# Input_amplifiers.net
KiCad netlist of a schematic drawn in Altium Designer
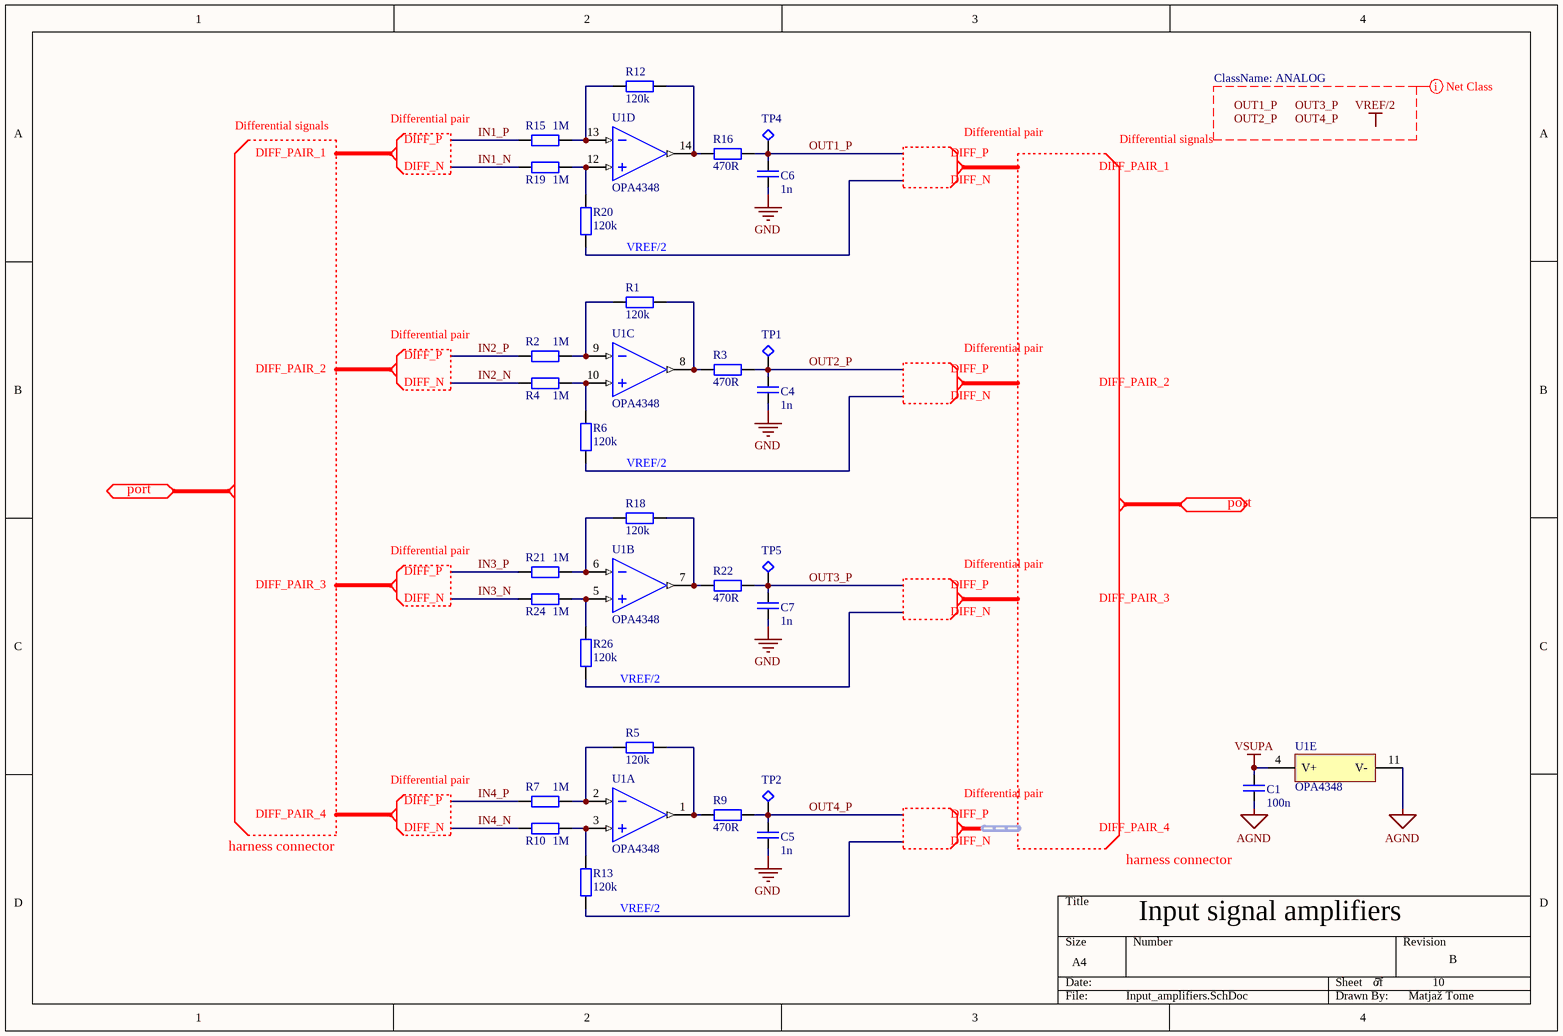
[diagram p0: Input_amplifiers.SchDoc]

(export (version "E")
  (design (tool "Eeschema 10.0.6"))
  (components
    (comp (ref "C1")
      (value "100n")
      (footprint "C_0603")
      (description "Generic capacitor")
      (libsource (lib "DAQ_REV_B") (part "Capacitor"))
    )
    (comp (ref "C4")
      (value "1n")
      (footprint "C_0603")
      (description "Generic capacitor")
      (libsource (lib "DAQ_REV_B") (part "Capacitor"))
    )
    (comp (ref "C5")
      (value "1n")
      (footprint "C_0603")
      (description "Generic capacitor")
      (libsource (lib "DAQ_REV_B") (part "Capacitor"))
    )
    (comp (ref "C6")
      (value "1n")
      (footprint "C_0603")
      (description "Generic capacitor")
      (libsource (lib "DAQ_REV_B") (part "Capacitor"))
    )
    (comp (ref "C7")
      (value "1n")
      (footprint "C_0603")
      (description "Generic capacitor")
      (libsource (lib "DAQ_REV_B") (part "Capacitor"))
    )
    (comp (ref "R1")
      (value "120k")
      (footprint "R_0603")
      (description "Generic resistor")
      (libsource (lib "DAQ_REV_B") (part "Resistor"))
    )
    (comp (ref "R2")
      (value "1M")
      (footprint "R_0603")
      (description "Generic resistor")
      (libsource (lib "DAQ_REV_B") (part "Resistor"))
    )
    (comp (ref "R3")
      (value "470R")
      (footprint "R_0603")
      (description "Generic resistor")
      (libsource (lib "DAQ_REV_B") (part "Resistor"))
    )
    (comp (ref "R4")
      (value "1M")
      (footprint "R_0603")
      (description "Generic resistor")
      (libsource (lib "DAQ_REV_B") (part "Resistor"))
    )
    (comp (ref "R5")
      (value "120k")
      (footprint "R_0603")
      (description "Generic resistor")
      (libsource (lib "DAQ_REV_B") (part "Resistor"))
    )
    (comp (ref "R6")
      (value "120k")
      (footprint "R_0603")
      (description "Generic resistor")
      (libsource (lib "DAQ_REV_B") (part "Resistor"))
    )
    (comp (ref "R7")
      (value "1M")
      (footprint "R_0603")
      (description "Generic resistor")
      (libsource (lib "DAQ_REV_B") (part "Resistor"))
    )
    (comp (ref "R9")
      (value "470R")
      (footprint "R_0603")
      (description "Generic resistor")
      (libsource (lib "DAQ_REV_B") (part "Resistor"))
    )
    (comp (ref "R10")
      (value "1M")
      (footprint "R_0603")
      (description "Generic resistor")
      (libsource (lib "DAQ_REV_B") (part "Resistor"))
    )
    (comp (ref "R12")
      (value "120k")
      (footprint "R_0603")
      (description "Generic resistor")
      (libsource (lib "DAQ_REV_B") (part "Resistor"))
    )
    (comp (ref "R13")
      (value "120k")
      (footprint "R_0603")
      (description "Generic resistor")
      (libsource (lib "DAQ_REV_B") (part "Resistor"))
    )
    (comp (ref "R15")
      (value "1M")
      (footprint "R_0603")
      (description "Generic resistor")
      (libsource (lib "DAQ_REV_B") (part "Resistor"))
    )
    (comp (ref "R16")
      (value "470R")
      (footprint "R_0603")
      (description "Generic resistor")
      (libsource (lib "DAQ_REV_B") (part "Resistor"))
    )
    (comp (ref "R18")
      (value "120k")
      (footprint "R_0603")
      (description "Generic resistor")
      (libsource (lib "DAQ_REV_B") (part "Resistor"))
    )
    (comp (ref "R19")
      (value "1M")
      (footprint "R_0603")
      (description "Generic resistor")
      (libsource (lib "DAQ_REV_B") (part "Resistor"))
    )
    (comp (ref "R20")
      (value "120k")
      (footprint "R_0603")
      (description "Generic resistor")
      (libsource (lib "DAQ_REV_B") (part "Resistor"))
    )
    (comp (ref "R21")
      (value "1M")
      (footprint "R_0603")
      (description "Generic resistor")
      (libsource (lib "DAQ_REV_B") (part "Resistor"))
    )
    (comp (ref "R22")
      (value "470R")
      (footprint "R_0603")
      (description "Generic resistor")
      (libsource (lib "DAQ_REV_B") (part "Resistor"))
    )
    (comp (ref "R24")
      (value "1M")
      (footprint "R_0603")
      (description "Generic resistor")
      (libsource (lib "DAQ_REV_B") (part "Resistor"))
    )
    (comp (ref "R26")
      (value "120k")
      (footprint "R_0603")
      (description "Generic resistor")
      (libsource (lib "DAQ_REV_B") (part "Resistor"))
    )
    (comp (ref "TP1")
      (value "testpoint")
      (footprint "TP1_FULL")
      (description "testpoint 1.5mm diameter no hole")
      (fields (field (name "PART NUMBER") "XXC0006"))
      (libsource (lib "DAQ_REV_B") (part "Test Point"))
    )
    (comp (ref "TP2")
      (value "testpoint")
      (footprint "TP1_FULL")
      (description "testpoint 1.5mm diameter no hole")
      (fields (field (name "PART NUMBER") "XXC0006"))
      (libsource (lib "DAQ_REV_B") (part "Test Point"))
    )
    (comp (ref "TP4")
      (value "testpoint")
      (footprint "TP1_FULL")
      (description "testpoint 1.5mm diameter no hole")
      (fields (field (name "PART NUMBER") "XXC0006"))
      (libsource (lib "DAQ_REV_B") (part "Test Point"))
    )
    (comp (ref "TP5")
      (value "testpoint")
      (footprint "TP1_FULL")
      (description "testpoint 1.5mm diameter no hole")
      (fields (field (name "PART NUMBER") "XXC0006"))
      (libsource (lib "DAQ_REV_B") (part "Test Point"))
    )
    (comp (ref "U1")
      (value "OPA4348")
      (description "1MHz, 45µA, CMOS, Rail-to-Rail OPERATIONAL AMPLIFIERS Value Line Series")
      (fields (field (name "PART NUMBER") "XOG0008") (field (name "MANUFACTURER") "Texas Instruments"))
      (libsource (lib "DAQ_REV_B") (part "OPA4348"))
    )
  )
  (nets
    (net (code "1") (name "/IN1_N") (class "Default") (node (ref "R19") (pin "1") (pintype "passive")))
    (net (code "2") (name "/IN1_P") (class "Default") (node (ref "R15") (pin "1") (pintype "passive")))
    (net (code "3") (name "/IN2_N") (class "Default") (node (ref "R4") (pin "1") (pintype "passive")))
    (net (code "4") (name "/IN2_P") (class "Default") (node (ref "R2") (pin "1") (pintype "passive")))
    (net (code "5") (name "/IN3_N") (class "Default") (node (ref "R24") (pin "1") (pintype "passive")))
    (net (code "6") (name "/IN3_P") (class "Default") (node (ref "R21") (pin "1") (pintype "passive")))
    (net (code "7") (name "/IN4_N") (class "Default") (node (ref "R10") (pin "1") (pintype "passive")))
    (net (code "8") (name "/IN4_P") (class "Default") (node (ref "R7") (pin "1") (pintype "passive")))
    (net (code "9") (name "/OUT1_P") (class "Default")
      (node (ref "C6") (pin "1") (pinfunction "1_1") (pintype "passive"))
      (node (ref "R16") (pin "2") (pintype "passive"))
      (node (ref "TP4") (pin "1") (pinfunction "1_1") (pintype "passive"))
    )
    (net (code "10") (name "/OUT2_P") (class "Default")
      (node (ref "C4") (pin "1") (pinfunction "1_1") (pintype "passive"))
      (node (ref "R3") (pin "2") (pintype "passive"))
      (node (ref "TP1") (pin "1") (pinfunction "1_1") (pintype "passive"))
    )
    (net (code "11") (name "/OUT3_P") (class "Default")
      (node (ref "C7") (pin "1") (pinfunction "1_1") (pintype "passive"))
      (node (ref "R22") (pin "2") (pintype "passive"))
      (node (ref "TP5") (pin "1") (pinfunction "1_1") (pintype "passive"))
    )
    (net (code "12") (name "/OUT4_P") (class "Default")
      (node (ref "C5") (pin "1") (pinfunction "1_1") (pintype "passive"))
      (node (ref "R9") (pin "2") (pintype "passive"))
      (node (ref "TP2") (pin "1") (pinfunction "1_1") (pintype "passive"))
    )
    (net (code "13") (name "AGND") (class "Default")
      (node (ref "C1") (pin "1") (pinfunction "1_1") (pintype "passive"))
      (node (ref "U1") (pin "11") (pinfunction "V-_11") (pintype "power_in"))
    )
    (net (code "14") (name "GND") (class "Default")
      (node (ref "C4") (pin "2") (pinfunction "2_2") (pintype "passive"))
      (node (ref "C5") (pin "2") (pinfunction "2_2") (pintype "passive"))
      (node (ref "C6") (pin "2") (pinfunction "2_2") (pintype "passive"))
      (node (ref "C7") (pin "2") (pinfunction "2_2") (pintype "passive"))
    )
    (net (code "15") (name "Net-(U1A-+IN_A)") (class "Default")
      (node (ref "R10") (pin "2") (pintype "passive"))
      (node (ref "R13") (pin "2") (pintype "passive"))
      (node (ref "U1") (pin "3") (pinfunction "+IN_A_3") (pintype "input"))
    )
    (net (code "16") (name "Net-(U1A--IN_A)") (class "Default")
      (node (ref "R5") (pin "1") (pintype "passive"))
      (node (ref "R7") (pin "2") (pintype "passive"))
      (node (ref "U1") (pin "2") (pinfunction "-IN_A_2") (pintype "input"))
    )
    (net (code "17") (name "Net-(U1A-OUT_A)") (class "Default")
      (node (ref "R5") (pin "2") (pintype "passive"))
      (node (ref "R9") (pin "1") (pintype "passive"))
      (node (ref "U1") (pin "1") (pinfunction "OUT_A_1") (pintype "output"))
    )
    (net (code "18") (name "Net-(U1B-+IN_B)") (class "Default")
      (node (ref "R24") (pin "2") (pintype "passive"))
      (node (ref "R26") (pin "2") (pintype "passive"))
      (node (ref "U1") (pin "5") (pinfunction "+IN_B_5") (pintype "input"))
    )
    (net (code "19") (name "Net-(U1B--IN_B)") (class "Default")
      (node (ref "R18") (pin "1") (pintype "passive"))
      (node (ref "R21") (pin "2") (pintype "passive"))
      (node (ref "U1") (pin "6") (pinfunction "-IN_B_6") (pintype "input"))
    )
    (net (code "20") (name "Net-(U1B-OUT_B)") (class "Default")
      (node (ref "R18") (pin "2") (pintype "passive"))
      (node (ref "R22") (pin "1") (pintype "passive"))
      (node (ref "U1") (pin "7") (pinfunction "OUT_B_7") (pintype "output"))
    )
    (net (code "21") (name "Net-(U1C-+IN_C)") (class "Default")
      (node (ref "R4") (pin "2") (pintype "passive"))
      (node (ref "R6") (pin "2") (pintype "passive"))
      (node (ref "U1") (pin "10") (pinfunction "+IN_C_10") (pintype "input"))
    )
    (net (code "22") (name "Net-(U1C--IN_C)") (class "Default")
      (node (ref "R1") (pin "1") (pintype "passive"))
      (node (ref "R2") (pin "2") (pintype "passive"))
      (node (ref "U1") (pin "9") (pinfunction "-IN_C_9") (pintype "input"))
    )
    (net (code "23") (name "Net-(U1C-OUT_C)") (class "Default")
      (node (ref "R1") (pin "2") (pintype "passive"))
      (node (ref "R3") (pin "1") (pintype "passive"))
      (node (ref "U1") (pin "8") (pinfunction "OUT_C_8") (pintype "output"))
    )
    (net (code "24") (name "Net-(U1D-+IN_D)") (class "Default")
      (node (ref "R19") (pin "2") (pintype "passive"))
      (node (ref "R20") (pin "2") (pintype "passive"))
      (node (ref "U1") (pin "12") (pinfunction "+IN_D_12") (pintype "input"))
    )
    (net (code "25") (name "Net-(U1D--IN_D)") (class "Default")
      (node (ref "R12") (pin "1") (pintype "passive"))
      (node (ref "R15") (pin "2") (pintype "passive"))
      (node (ref "U1") (pin "13") (pinfunction "-IN_D_13") (pintype "input"))
    )
    (net (code "26") (name "Net-(U1D-OUT_D)") (class "Default")
      (node (ref "R12") (pin "2") (pintype "passive"))
      (node (ref "R16") (pin "1") (pintype "passive"))
      (node (ref "U1") (pin "14") (pinfunction "OUT_D_14") (pintype "output"))
    )
    (net (code "28") (name "VSUPA") (class "Default")
      (node (ref "C1") (pin "2") (pinfunction "2_2") (pintype "passive"))
      (node (ref "U1") (pin "4") (pinfunction "V+_4") (pintype "power_in"))
    )
    (net (code "29") (name "unconnected-(R6-Pad1)") (class "Default")
      (node (ref "R6") (pin "1") (pintype "passive"))
    )
    (net (code "30") (name "unconnected-(R13-Pad1)") (class "Default")
      (node (ref "R13") (pin "1") (pintype "passive"))
    )
    (net (code "31") (name "unconnected-(R20-Pad1)") (class "Default")
      (node (ref "R20") (pin "1") (pintype "passive"))
    )
    (net (code "32") (name "unconnected-(R26-Pad1)") (class "Default")
      (node (ref "R26") (pin "1") (pintype "passive"))
    )
  )
)
